# STB_DUTConnector.net
KiCad netlist of a schematic drawn in Altium Designer
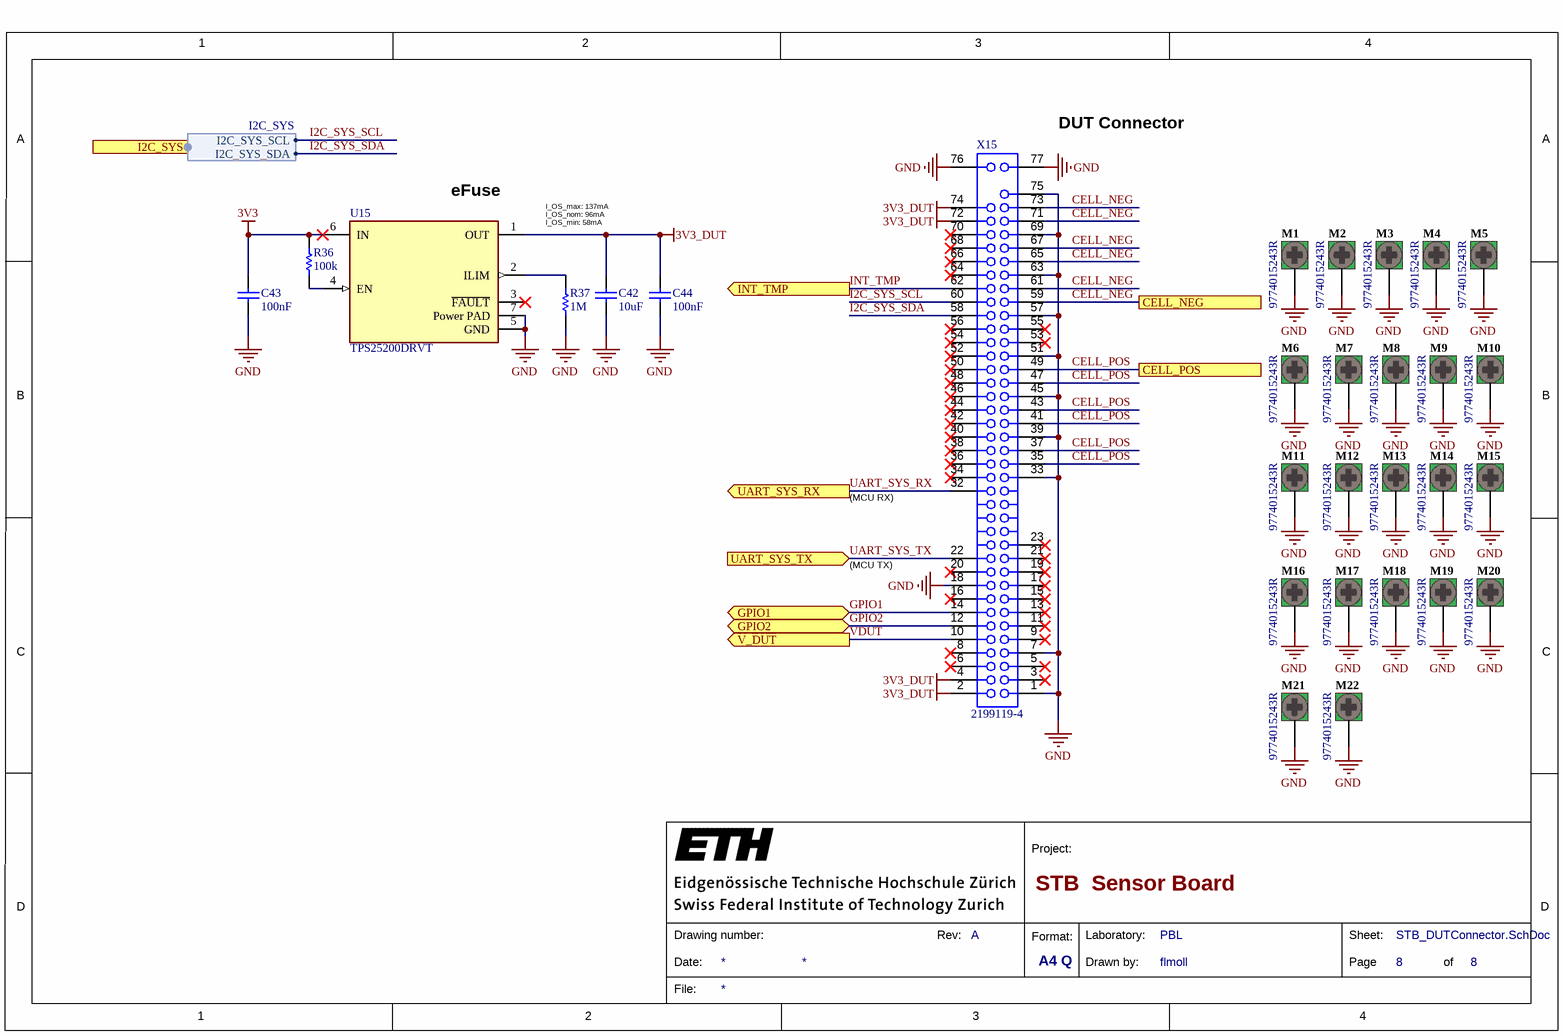
[diagram p0: STB_DUTConnector.SchDoc]

(export (version "E")
  (design (tool "Eeschema 10.0.6"))
  (components
    (comp (ref "C42")
      (value "10uF")
      (footprint "CAPC0603(1608)100_L")
      (description "CAP 10uF 10V ±10% 0603 (1608 Metric) Thickness 1mm SMD")
      (fields (field (name "TOLERANCE") "Â±10%") (field (name "MANUFACTURER") "Samsung"))
      (libsource (lib "Altium Content Vault") (part "CMP-1035-02799-1"))
    )
    (comp (ref "C43")
      (value "100nF")
      (footprint "CAPC1050X55X23LL05T13")
      (description "Chip Capacitor, 100 nF, +/- 10%, 16 V, -55 to 125 degC, 0402 (1005 Metric), RoHS, Tape and Reel")
      (fields
        (field (name "MANUFACTURER") "Samsung Electro-Mechanics")
        (field (name "MANUFACTURER PART NUMBER") "CL05B104KO5NNNC")
      )
      (libsource (lib "Altium Content Vault") (part "CAP-NP-2"))
    )
    (comp (ref "C44")
      (value "100nF")
      (footprint "CAPC1050X55X23LL05T13")
      (description "Chip Capacitor, 100 nF, +/- 10%, 16 V, -55 to 125 degC, 0402 (1005 Metric), RoHS, Tape and Reel")
      (fields
        (field (name "MANUFACTURER") "Samsung Electro-Mechanics")
        (field (name "MANUFACTURER PART NUMBER") "CL05B104KO5NNNC")
      )
      (libsource (lib "Altium Content Vault") (part "CAP-NP-2"))
    )
    (comp (ref "M1")
      (value "9774015243R")
      (footprint "9774015243R")
      (description "RND STANDOFF M2X0.4 STEEL 1.5MM")
      (fields (field (name "MANUFACTURER") "Wurth Electronics"))
      (libsource (lib "ETHZ Vault") (part "Hole"))
    )
    (comp (ref "M2")
      (value "9774015243R")
      (footprint "9774015243R")
      (description "RND STANDOFF M2X0.4 STEEL 1.5MM")
      (fields (field (name "MANUFACTURER") "Wurth Electronics"))
      (libsource (lib "ETHZ Vault") (part "Hole"))
    )
    (comp (ref "M3")
      (value "9774015243R")
      (footprint "9774015243R")
      (description "RND STANDOFF M2X0.4 STEEL 1.5MM")
      (fields (field (name "MANUFACTURER") "Wurth Electronics"))
      (libsource (lib "ETHZ Vault") (part "Hole"))
    )
    (comp (ref "M4")
      (value "9774015243R")
      (footprint "9774015243R")
      (description "RND STANDOFF M2X0.4 STEEL 1.5MM")
      (fields (field (name "MANUFACTURER") "Wurth Electronics"))
      (libsource (lib "ETHZ Vault") (part "Hole"))
    )
    (comp (ref "M5")
      (value "9774015243R")
      (footprint "9774015243R")
      (description "RND STANDOFF M2X0.4 STEEL 1.5MM")
      (fields (field (name "MANUFACTURER") "Wurth Electronics"))
      (libsource (lib "ETHZ Vault") (part "Hole"))
    )
    (comp (ref "M6")
      (value "9774015243R")
      (footprint "9774015243R")
      (description "RND STANDOFF M2X0.4 STEEL 1.5MM")
      (fields (field (name "MANUFACTURER") "Wurth Electronics"))
      (libsource (lib "ETHZ Vault") (part "Hole"))
    )
    (comp (ref "M7")
      (value "9774015243R")
      (footprint "9774015243R")
      (description "RND STANDOFF M2X0.4 STEEL 1.5MM")
      (fields (field (name "MANUFACTURER") "Wurth Electronics"))
      (libsource (lib "ETHZ Vault") (part "Hole"))
    )
    (comp (ref "M8")
      (value "9774015243R")
      (footprint "9774015243R")
      (description "RND STANDOFF M2X0.4 STEEL 1.5MM")
      (fields (field (name "MANUFACTURER") "Wurth Electronics"))
      (libsource (lib "ETHZ Vault") (part "Hole"))
    )
    (comp (ref "M9")
      (value "9774015243R")
      (footprint "9774015243R")
      (description "RND STANDOFF M2X0.4 STEEL 1.5MM")
      (fields (field (name "MANUFACTURER") "Wurth Electronics"))
      (libsource (lib "ETHZ Vault") (part "Hole"))
    )
    (comp (ref "M10")
      (value "9774015243R")
      (footprint "9774015243R")
      (description "RND STANDOFF M2X0.4 STEEL 1.5MM")
      (fields (field (name "MANUFACTURER") "Wurth Electronics"))
      (libsource (lib "ETHZ Vault") (part "Hole"))
    )
    (comp (ref "M11")
      (value "9774015243R")
      (footprint "9774015243R")
      (description "RND STANDOFF M2X0.4 STEEL 1.5MM")
      (fields (field (name "MANUFACTURER") "Wurth Electronics"))
      (libsource (lib "ETHZ Vault") (part "Hole"))
    )
    (comp (ref "M12")
      (value "9774015243R")
      (footprint "9774015243R")
      (description "RND STANDOFF M2X0.4 STEEL 1.5MM")
      (fields (field (name "MANUFACTURER") "Wurth Electronics"))
      (libsource (lib "ETHZ Vault") (part "Hole"))
    )
    (comp (ref "M13")
      (value "9774015243R")
      (footprint "9774015243R")
      (description "RND STANDOFF M2X0.4 STEEL 1.5MM")
      (fields (field (name "MANUFACTURER") "Wurth Electronics"))
      (libsource (lib "ETHZ Vault") (part "Hole"))
    )
    (comp (ref "M14")
      (value "9774015243R")
      (footprint "9774015243R")
      (description "RND STANDOFF M2X0.4 STEEL 1.5MM")
      (fields (field (name "MANUFACTURER") "Wurth Electronics"))
      (libsource (lib "ETHZ Vault") (part "Hole"))
    )
    (comp (ref "M15")
      (value "9774015243R")
      (footprint "9774015243R")
      (description "RND STANDOFF M2X0.4 STEEL 1.5MM")
      (fields (field (name "MANUFACTURER") "Wurth Electronics"))
      (libsource (lib "ETHZ Vault") (part "Hole"))
    )
    (comp (ref "M16")
      (value "9774015243R")
      (footprint "9774015243R")
      (description "RND STANDOFF M2X0.4 STEEL 1.5MM")
      (fields (field (name "MANUFACTURER") "Wurth Electronics"))
      (libsource (lib "ETHZ Vault") (part "Hole"))
    )
    (comp (ref "M17")
      (value "9774015243R")
      (footprint "9774015243R")
      (description "RND STANDOFF M2X0.4 STEEL 1.5MM")
      (fields (field (name "MANUFACTURER") "Wurth Electronics"))
      (libsource (lib "ETHZ Vault") (part "Hole"))
    )
    (comp (ref "M18")
      (value "9774015243R")
      (footprint "9774015243R")
      (description "RND STANDOFF M2X0.4 STEEL 1.5MM")
      (fields (field (name "MANUFACTURER") "Wurth Electronics"))
      (libsource (lib "ETHZ Vault") (part "Hole"))
    )
    (comp (ref "M19")
      (value "9774015243R")
      (footprint "9774015243R")
      (description "RND STANDOFF M2X0.4 STEEL 1.5MM")
      (fields (field (name "MANUFACTURER") "Wurth Electronics"))
      (libsource (lib "ETHZ Vault") (part "Hole"))
    )
    (comp (ref "M20")
      (value "9774015243R")
      (footprint "9774015243R")
      (description "RND STANDOFF M2X0.4 STEEL 1.5MM")
      (fields (field (name "MANUFACTURER") "Wurth Electronics"))
      (libsource (lib "ETHZ Vault") (part "Hole"))
    )
    (comp (ref "M21")
      (value "9774015243R")
      (footprint "9774015243R")
      (description "RND STANDOFF M2X0.4 STEEL 1.5MM")
      (fields (field (name "MANUFACTURER") "Wurth Electronics"))
      (libsource (lib "ETHZ Vault") (part "Hole"))
    )
    (comp (ref "M22")
      (value "9774015243R")
      (footprint "9774015243R")
      (description "RND STANDOFF M2X0.4 STEEL 1.5MM")
      (fields (field (name "MANUFACTURER") "Wurth Electronics"))
      (libsource (lib "ETHZ Vault") (part "Hole"))
    )
    (comp (ref "R36")
      (value "100k")
      (footprint "RESC1005X40X25LL05T10")
      (fields
        (field (name "PART NUMBER") "RC0402FR-07100KL")
        (field (name "MANUFACTURER") "Yageo / Phycomp")
        (field (name "TOLERANCE") "1%")
      )
      (libsource (lib "Altium Content Vault") (part "RES"))
    )
    (comp (ref "R37")
      (value "1M")
      (footprint "RESC1005X40X25LL05T10")
      (fields
        (field (name "MANUFACTURER") "Yageo / Phycomp")
        (field (name "PART NUMBER") "RC0402FR-071ML")
        (field (name "TOLERANCE") "1%")
      )
      (libsource (lib "Altium Content Vault") (part "RES"))
    )
    (comp (ref "U15")
      (value "TPS25200DRVT")
      (footprint "FP-DRV0006A-MFG")
      (description "IC PWR MGR EFUSE 6.5V 2.8A 6SON")
      (fields (field (name "VOLTAGE") "6.5V") (field (name "MANUFACTURER") "Texas Instruments"))
      (libsource (lib "Altium Content Vault") (part "c371350b44384884d2a4ba1f5a1984b"))
    )
    (comp (ref "X15")
      (value "2199119-4")
      (footprint "2199119-4")
      (description "67 Position Female Connector M.2 (NGFF) Mini Card Gold 0.020\" (0.50mm) Black")
      (fields
        (field (name "MANUFACTURER") "TE Connectivity")
        (field (name "MANUFACTURER PART NUMBER") "2199230-4")
      )
      (libsource (lib "ETHZ Vault") (part "2199119-4"))
    )
  )
  (nets
    (net (code "2") (name "/CELL_NEG") (class "Default")
      (node (ref "X15") (pin "59") (pinfunction "59_59") (pintype "passive"))
      (node (ref "X15") (pin "61") (pinfunction "61_61") (pintype "passive"))
      (node (ref "X15") (pin "65") (pinfunction "65_65") (pintype "passive"))
      (node (ref "X15") (pin "67") (pinfunction "67_67") (pintype "passive"))
      (node (ref "X15") (pin "71") (pinfunction "71_71") (pintype "passive"))
      (node (ref "X15") (pin "73") (pinfunction "73_73") (pintype "passive"))
    )
    (net (code "3") (name "/CELL_POS") (class "Default")
      (node (ref "X15") (pin "35") (pinfunction "35_35") (pintype "passive"))
      (node (ref "X15") (pin "37") (pinfunction "37_37") (pintype "passive"))
      (node (ref "X15") (pin "41") (pinfunction "41_41") (pintype "passive"))
      (node (ref "X15") (pin "43") (pinfunction "43_43") (pintype "passive"))
      (node (ref "X15") (pin "47") (pinfunction "47_47") (pintype "passive"))
      (node (ref "X15") (pin "49") (pinfunction "49_49") (pintype "passive"))
    )
    (net (code "4") (name "/GPIO1") (class "Default")
      (node (ref "X15") (pin "14") (pinfunction "14_14") (pintype "passive"))
    )
    (net (code "5") (name "/GPIO2") (class "Default")
      (node (ref "X15") (pin "12") (pinfunction "12_12") (pintype "passive"))
    )
    (net (code "6") (name "/I2C_SYS_SCL") (class "Default")
      (node (ref "X15") (pin "60") (pinfunction "55_60") (pintype "passive"))
    )
    (net (code "7") (name "/I2C_SYS_SDA") (class "Default")
      (node (ref "X15") (pin "58") (pinfunction "54_58") (pintype "passive"))
    )
    (net (code "8") (name "/INT_TMP") (class "Default")
      (node (ref "X15") (pin "62") (pinfunction "62_62") (pintype "passive"))
    )
    (net (code "9") (name "/UART_SYS_RX") (class "Default")
      (node (ref "X15") (pin "32") (pinfunction "32_32") (pintype "passive"))
    )
    (net (code "10") (name "/UART_SYS_TX") (class "Default")
      (node (ref "X15") (pin "22") (pinfunction "22_22") (pintype "passive"))
    )
    (net (code "11") (name "/VDUT") (class "Default")
      (node (ref "X15") (pin "10") (pinfunction "10_10") (pintype "passive"))
    )
    (net (code "13") (name "3V3") (class "Default")
      (node (ref "C43") (pin "2") (pinfunction "2_2") (pintype "passive"))
      (node (ref "R36") (pin "1") (pinfunction "1_1") (pintype "passive"))
      (node (ref "U15") (pin "6") (pinfunction "IN_6") (pintype "open_emitter"))
    )
    (net (code "14") (name "3V3_DUT") (class "Default")
      (node (ref "C42") (pin "2") (pinfunction "2_2") (pintype "passive"))
      (node (ref "C44") (pin "2") (pinfunction "2_2") (pintype "passive"))
      (node (ref "U15") (pin "1") (pinfunction "OUT_1") (pintype "power_in"))
      (node (ref "X15") (pin "2") (pinfunction "2_2") (pintype "passive"))
      (node (ref "X15") (pin "4") (pinfunction "4_4") (pintype "passive"))
      (node (ref "X15") (pin "72") (pinfunction "72_72") (pintype "passive"))
      (node (ref "X15") (pin "74") (pinfunction "74_74") (pintype "passive"))
    )
    (net (code "15") (name "GND") (class "Default")
      (node (ref "C42") (pin "1") (pinfunction "1_1") (pintype "passive"))
      (node (ref "C43") (pin "1") (pinfunction "1_1") (pintype "passive"))
      (node (ref "C44") (pin "1") (pinfunction "1_1") (pintype "passive"))
      (node (ref "M1") (pin "1") (pinfunction "1_1") (pintype "passive"))
      (node (ref "M10") (pin "1") (pinfunction "1_1") (pintype "passive"))
      (node (ref "M11") (pin "1") (pinfunction "1_1") (pintype "passive"))
      (node (ref "M12") (pin "1") (pinfunction "1_1") (pintype "passive"))
      (node (ref "M13") (pin "1") (pinfunction "1_1") (pintype "passive"))
      (node (ref "M14") (pin "1") (pinfunction "1_1") (pintype "passive"))
      (node (ref "M15") (pin "1") (pinfunction "1_1") (pintype "passive"))
      (node (ref "M16") (pin "1") (pinfunction "1_1") (pintype "passive"))
      (node (ref "M17") (pin "1") (pinfunction "1_1") (pintype "passive"))
      (node (ref "M18") (pin "1") (pinfunction "1_1") (pintype "passive"))
      (node (ref "M19") (pin "1") (pinfunction "1_1") (pintype "passive"))
      (node (ref "M2") (pin "1") (pinfunction "1_1") (pintype "passive"))
      (node (ref "M20") (pin "1") (pinfunction "1_1") (pintype "passive"))
      (node (ref "M21") (pin "1") (pinfunction "1_1") (pintype "passive"))
      (node (ref "M22") (pin "1") (pinfunction "1_1") (pintype "passive"))
      (node (ref "M3") (pin "1") (pinfunction "1_1") (pintype "passive"))
      (node (ref "M4") (pin "1") (pinfunction "1_1") (pintype "passive"))
      (node (ref "M5") (pin "1") (pinfunction "1_1") (pintype "passive"))
      (node (ref "M6") (pin "1") (pinfunction "1_1") (pintype "passive"))
      (node (ref "M7") (pin "1") (pinfunction "1_1") (pintype "passive"))
      (node (ref "M8") (pin "1") (pinfunction "1_1") (pintype "passive"))
      (node (ref "M9") (pin "1") (pinfunction "1_1") (pintype "passive"))
      (node (ref "R37") (pin "1") (pinfunction "1_1") (pintype "passive"))
      (node (ref "U15") (pin "5") (pinfunction "GND_5") (pintype "power_in"))
      (node (ref "U15") (pin "7") (pinfunction "Power_PAD_7") (pintype "power_in"))
      (node (ref "X15") (pin "1") (pinfunction "1_1") (pintype "passive"))
      (node (ref "X15") (pin "18") (pinfunction "18_18") (pintype "passive"))
      (node (ref "X15") (pin "33") (pinfunction "33_33") (pintype "passive"))
      (node (ref "X15") (pin "39") (pinfunction "39_39") (pintype "passive"))
      (node (ref "X15") (pin "45") (pinfunction "45_45") (pintype "passive"))
      (node (ref "X15") (pin "51") (pinfunction "51_51") (pintype "passive"))
      (node (ref "X15") (pin "57") (pinfunction "57_57") (pintype "passive"))
      (node (ref "X15") (pin "63") (pinfunction "63_63") (pintype "passive"))
      (node (ref "X15") (pin "69") (pinfunction "69_69") (pintype "passive"))
      (node (ref "X15") (pin "7") (pinfunction "7_7") (pintype "passive"))
      (node (ref "X15") (pin "75") (pinfunction "75_75") (pintype "passive"))
      (node (ref "X15") (pin "76") (pinfunction "76_76") (pintype "passive"))
      (node (ref "X15") (pin "77") (pinfunction "77_77") (pintype "passive"))
    )
    (net (code "16") (name "Net-(U15-EN)") (class "Default")
      (node (ref "R36") (pin "2") (pinfunction "2_2") (pintype "passive"))
      (node (ref "U15") (pin "4") (pinfunction "EN_4") (pintype "input"))
    )
    (net (code "17") (name "Net-(U15-ILIM)") (class "Default")
      (node (ref "R37") (pin "2") (pinfunction "2_2") (pintype "passive"))
      (node (ref "U15") (pin "2") (pinfunction "ILIM_2") (pintype "output"))
    )
    (net (code "18") (name "unconnected-(U15-~{FAULT}-Pad3)") (class "Default")
      (node (ref "U15") (pin "3") (pinfunction "~{FAULT}_3") (pintype "open_collector+no_connect"))
    )
    (net (code "19") (name "unconnected-(X15-51-Pad52)") (class "Default")
      (node (ref "X15") (pin "52") (pinfunction "51_52") (pintype "passive+no_connect"))
    )
    (net (code "20") (name "unconnected-(X15-52-Pad54)") (class "Default")
      (node (ref "X15") (pin "54") (pinfunction "52_54") (pintype "passive+no_connect"))
    )
    (net (code "21") (name "unconnected-(X15-53-Pad56)") (class "Default")
      (node (ref "X15") (pin "56") (pinfunction "53_56") (pintype "passive+no_connect"))
    )
    (net (code "22") (name "unconnected-(X15-Pad3)") (class "Default")
      (node (ref "X15") (pin "3") (pinfunction "3_3") (pintype "passive+no_connect"))
    )
    (net (code "23") (name "unconnected-(X15-Pad5)") (class "Default")
      (node (ref "X15") (pin "5") (pinfunction "5_5") (pintype "passive+no_connect"))
    )
    (net (code "24") (name "unconnected-(X15-Pad6)") (class "Default")
      (node (ref "X15") (pin "6") (pinfunction "6_6") (pintype "passive+no_connect"))
    )
    (net (code "25") (name "unconnected-(X15-Pad8)") (class "Default")
      (node (ref "X15") (pin "8") (pinfunction "8_8") (pintype "passive+no_connect"))
    )
    (net (code "26") (name "unconnected-(X15-Pad9)") (class "Default")
      (node (ref "X15") (pin "9") (pinfunction "9_9") (pintype "passive+no_connect"))
    )
    (net (code "27") (name "unconnected-(X15-Pad11)") (class "Default")
      (node (ref "X15") (pin "11") (pinfunction "11_11") (pintype "passive+no_connect"))
    )
    (net (code "28") (name "unconnected-(X15-Pad13)") (class "Default")
      (node (ref "X15") (pin "13") (pinfunction "13_13") (pintype "passive+no_connect"))
    )
    (net (code "29") (name "unconnected-(X15-Pad15)") (class "Default")
      (node (ref "X15") (pin "15") (pinfunction "15_15") (pintype "passive+no_connect"))
    )
    (net (code "30") (name "unconnected-(X15-Pad16)") (class "Default")
      (node (ref "X15") (pin "16") (pinfunction "16_16") (pintype "passive+no_connect"))
    )
    (net (code "31") (name "unconnected-(X15-Pad17)") (class "Default")
      (node (ref "X15") (pin "17") (pinfunction "17_17") (pintype "passive+no_connect"))
    )
    (net (code "32") (name "unconnected-(X15-Pad19)") (class "Default")
      (node (ref "X15") (pin "19") (pinfunction "19_19") (pintype "passive+no_connect"))
    )
    (net (code "33") (name "unconnected-(X15-Pad20)") (class "Default")
      (node (ref "X15") (pin "20") (pinfunction "20_20") (pintype "passive+no_connect"))
    )
    (net (code "34") (name "unconnected-(X15-Pad21)") (class "Default")
      (node (ref "X15") (pin "21") (pinfunction "21_21") (pintype "passive+no_connect"))
    )
    (net (code "35") (name "unconnected-(X15-Pad23)") (class "Default")
      (node (ref "X15") (pin "23") (pinfunction "23_23") (pintype "passive+no_connect"))
    )
    (net (code "36") (name "unconnected-(X15-Pad34)") (class "Default")
      (node (ref "X15") (pin "34") (pinfunction "34_34") (pintype "passive+no_connect"))
    )
    (net (code "37") (name "unconnected-(X15-Pad36)") (class "Default")
      (node (ref "X15") (pin "36") (pinfunction "36_36") (pintype "passive+no_connect"))
    )
    (net (code "38") (name "unconnected-(X15-Pad38)") (class "Default")
      (node (ref "X15") (pin "38") (pinfunction "38_38") (pintype "passive+no_connect"))
    )
    (net (code "39") (name "unconnected-(X15-Pad40)") (class "Default")
      (node (ref "X15") (pin "40") (pinfunction "40_40") (pintype "passive+no_connect"))
    )
    (net (code "40") (name "unconnected-(X15-Pad42)") (class "Default")
      (node (ref "X15") (pin "42") (pinfunction "42_42") (pintype "passive+no_connect"))
    )
    (net (code "41") (name "unconnected-(X15-Pad44)") (class "Default")
      (node (ref "X15") (pin "44") (pinfunction "44_44") (pintype "passive+no_connect"))
    )
    (net (code "42") (name "unconnected-(X15-Pad46)") (class "Default")
      (node (ref "X15") (pin "46") (pinfunction "46_46") (pintype "passive+no_connect"))
    )
    (net (code "43") (name "unconnected-(X15-Pad48)") (class "Default")
      (node (ref "X15") (pin "48") (pinfunction "48_48") (pintype "passive+no_connect"))
    )
    (net (code "44") (name "unconnected-(X15-Pad50)") (class "Default")
      (node (ref "X15") (pin "50") (pinfunction "50_50") (pintype "passive+no_connect"))
    )
    (net (code "45") (name "unconnected-(X15-Pad53)") (class "Default")
      (node (ref "X15") (pin "53") (pinfunction "53_53") (pintype "passive+no_connect"))
    )
    (net (code "46") (name "unconnected-(X15-Pad55)") (class "Default")
      (node (ref "X15") (pin "55") (pinfunction "55_55") (pintype "passive+no_connect"))
    )
    (net (code "47") (name "unconnected-(X15-Pad64)") (class "Default")
      (node (ref "X15") (pin "64") (pinfunction "64_64") (pintype "passive+no_connect"))
    )
    (net (code "48") (name "unconnected-(X15-Pad66)") (class "Default")
      (node (ref "X15") (pin "66") (pinfunction "66_66") (pintype "passive+no_connect"))
    )
    (net (code "49") (name "unconnected-(X15-Pad68)") (class "Default")
      (node (ref "X15") (pin "68") (pinfunction "68_68") (pintype "passive+no_connect"))
    )
    (net (code "50") (name "unconnected-(X15-Pad70)") (class "Default")
      (node (ref "X15") (pin "70") (pinfunction "70_70") (pintype "passive+no_connect"))
    )
  )
)
